# module.net
KiCad netlist of a schematic drawn in Altium Designer
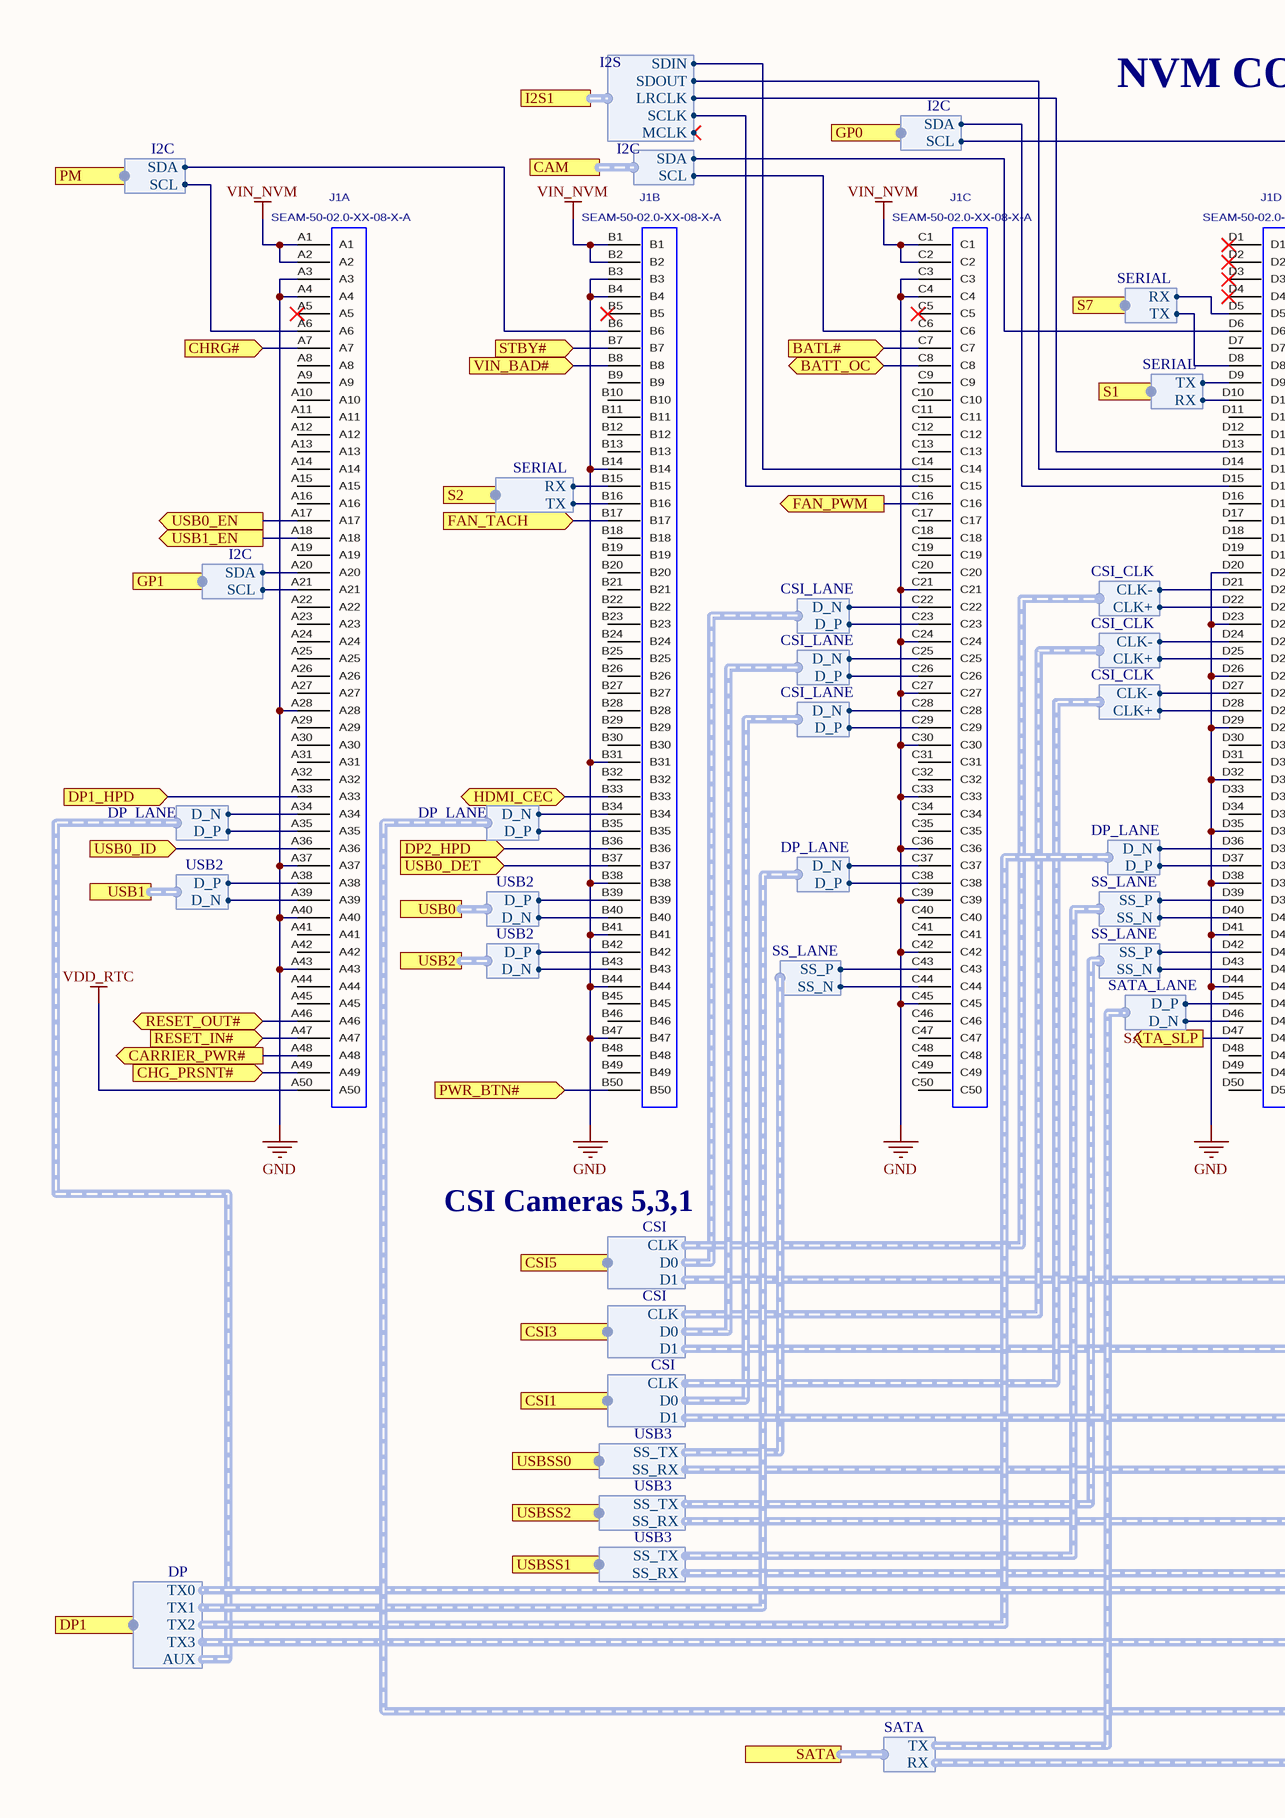
[diagram p0: module.SchDoc, left]
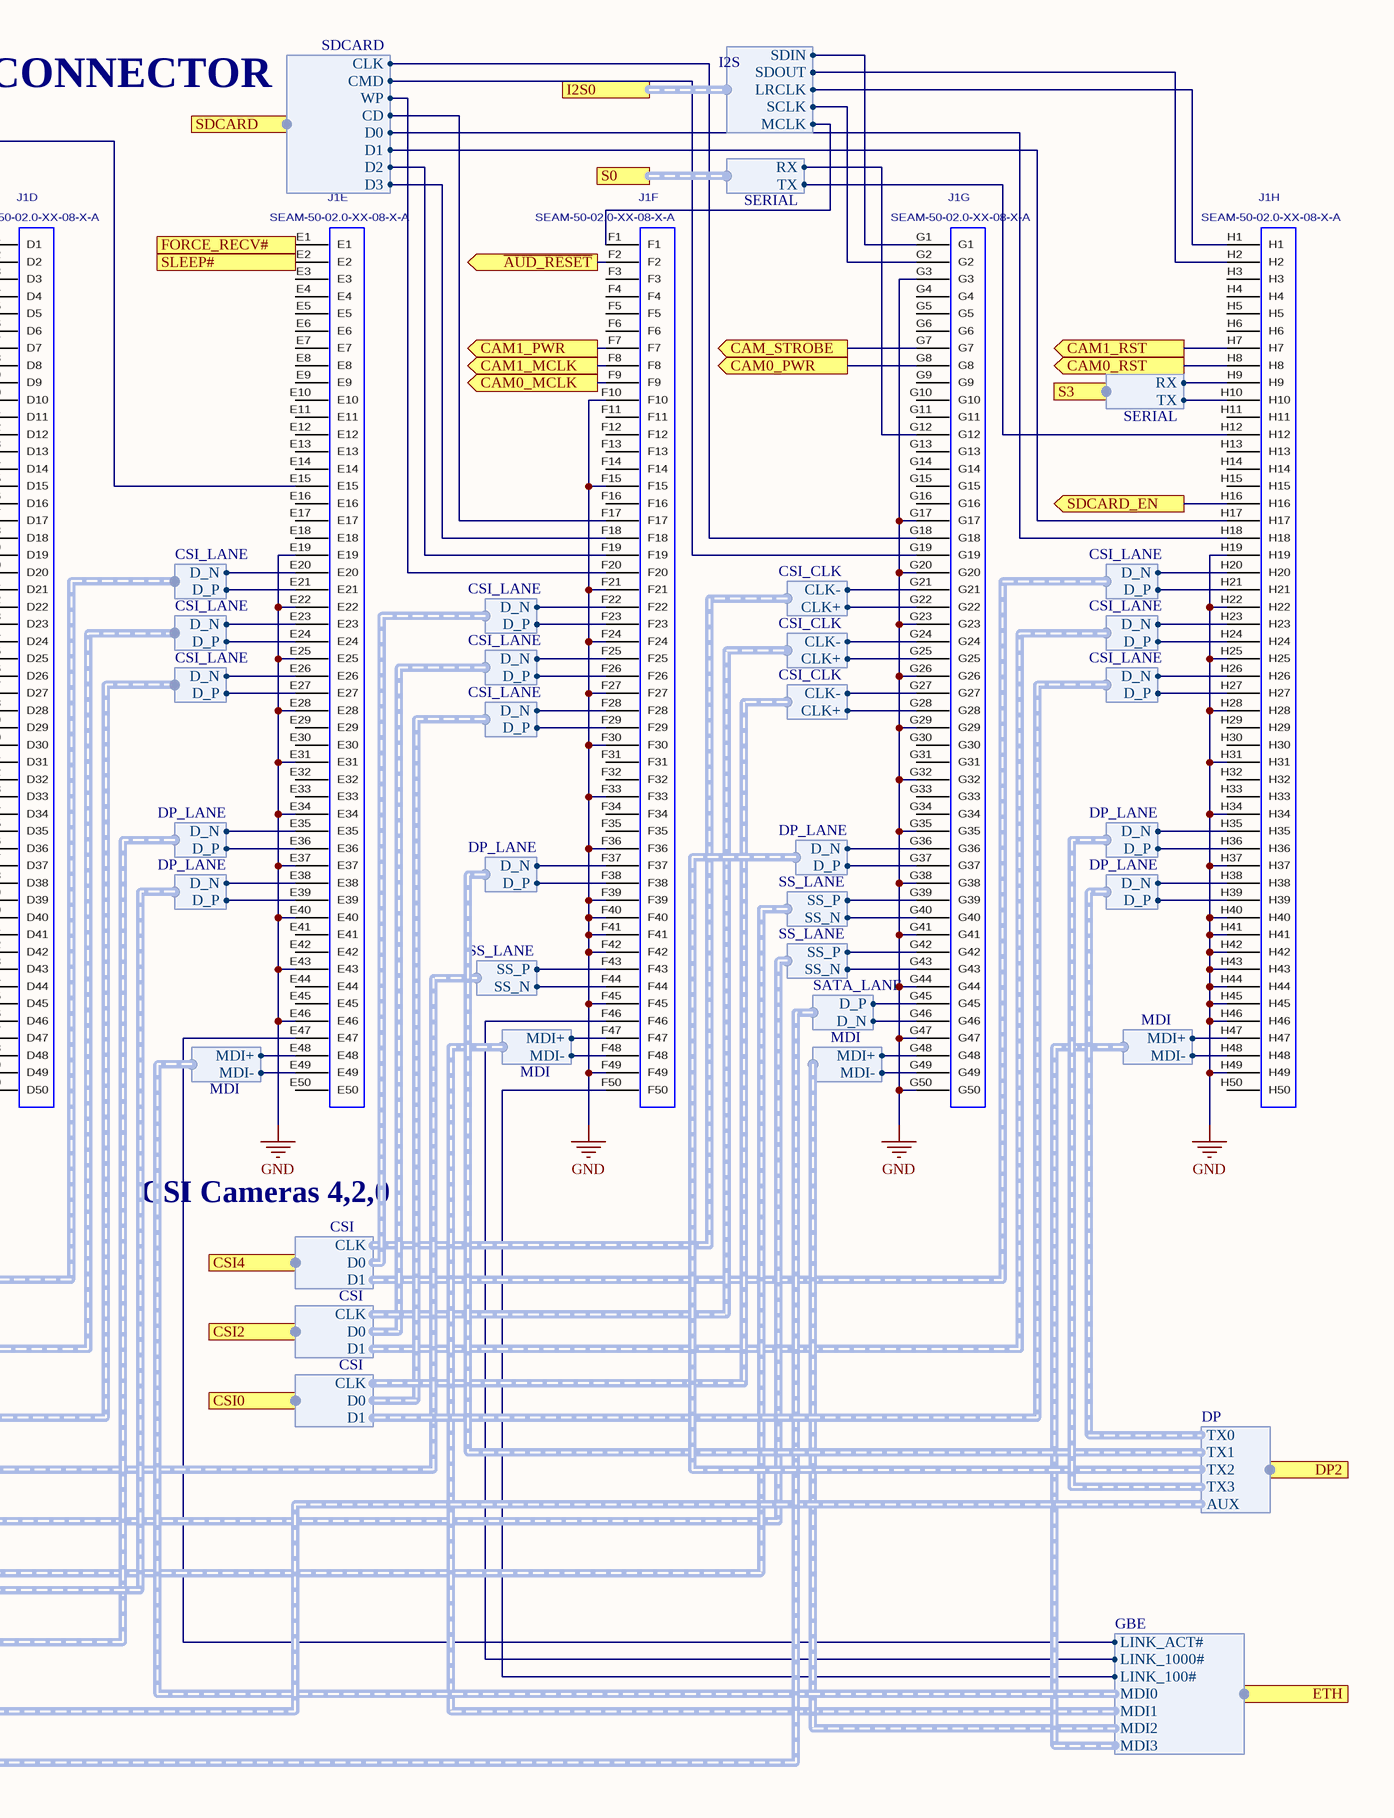
[diagram p1: module.SchDoc, right]

(export (version "E")
  (design (tool "Eeschema 10.0.6"))
  (components
    (comp (ref "J1")
      (value "SEAM-50-02.0-XX-08-X-A")
      (footprint "SEAM-50-02.0-XX-08-X-A")
      (description "0.050\" TERMINAL ASSEMBLY.")
      (fields (field (name "MANUFACTURER") "SAMTEC") (field (name "CREATED") "December 10, 2015 -Wendy Xin"))
      (libsource (lib "SEAM-50-02.0-XX-08-X-A") (part "SEAM-50-02.0-XX-08-X-A"))
    )
  )
  (nets
    (net (code "26") (name "/AUD_RESET") (class "Default")
      (node (ref "J1") (pin "F2") (pinfunction "F2_F2") (pintype "passive"))
    )
    (net (code "27") (name "/BATL#") (class "Default")
      (node (ref "J1") (pin "C7") (pinfunction "C7_C7") (pintype "passive"))
    )
    (net (code "28") (name "/BATT_OC") (class "Default")
      (node (ref "J1") (pin "C8") (pinfunction "C8_C8") (pintype "passive"))
    )
    (net (code "29") (name "/CAM0_MCLK") (class "Default")
      (node (ref "J1") (pin "F9") (pinfunction "F9_F9") (pintype "passive"))
    )
    (net (code "30") (name "/CAM0_PWR") (class "Default")
      (node (ref "J1") (pin "G8") (pinfunction "G8_G8") (pintype "passive"))
    )
    (net (code "31") (name "/CAM0_RST") (class "Default")
      (node (ref "J1") (pin "H8") (pinfunction "H8_H8") (pintype "passive"))
    )
    (net (code "32") (name "/CAM1_MCLK") (class "Default")
      (node (ref "J1") (pin "F8") (pinfunction "F8_F8") (pintype "passive"))
    )
    (net (code "33") (name "/CAM1_PWR") (class "Default")
      (node (ref "J1") (pin "F7") (pinfunction "F7_F7") (pintype "passive"))
    )
    (net (code "34") (name "/CAM1_RST") (class "Default")
      (node (ref "J1") (pin "H7") (pinfunction "H7_H7") (pintype "passive"))
    )
    (net (code "35") (name "/CAM_STROBE") (class "Default")
      (node (ref "J1") (pin "G7") (pinfunction "G7_G7") (pintype "passive"))
    )
    (net (code "36") (name "/CARRIER_PWR#") (class "Default")
      (node (ref "J1") (pin "A48") (pinfunction "A48_A48") (pintype "passive"))
    )
    (net (code "37") (name "/CD") (class "Default")
      (node (ref "J1") (pin "F17") (pinfunction "F17_F17") (pintype "passive"))
    )
    (net (code "38") (name "/CHG_PRSNT#") (class "Default")
      (node (ref "J1") (pin "A49") (pinfunction "A49_A49") (pintype "passive"))
    )
    (net (code "39") (name "/CHRG#") (class "Default")
      (node (ref "J1") (pin "A7") (pinfunction "A7_A7") (pintype "passive"))
    )
    (net (code "40") (name "/CMD") (class "Default")
      (node (ref "J1") (pin "G19") (pinfunction "G19_G19") (pintype "passive"))
    )
    (net (code "47") (name "/D2") (class "Default")
      (node (ref "J1") (pin "F19") (pinfunction "F19_F19") (pintype "passive"))
    )
    (net (code "48") (name "/D3") (class "Default")
      (node (ref "J1") (pin "F18") (pinfunction "F18_F18") (pintype "passive"))
    )
    (net (code "49") (name "/DP1_HPD") (class "Default")
      (node (ref "J1") (pin "A33") (pinfunction "A33_A33") (pintype "passive"))
    )
    (net (code "51") (name "/DP2_HPD") (class "Default")
      (node (ref "J1") (pin "B36") (pinfunction "B36_B36") (pintype "passive"))
    )
    (net (code "54") (name "/FAN_PWM") (class "Default")
      (node (ref "J1") (pin "C16") (pinfunction "C16_C16") (pintype "passive"))
    )
    (net (code "55") (name "/FAN_TACH") (class "Default")
      (node (ref "J1") (pin "B17") (pinfunction "B17_B17") (pintype "passive"))
    )
    (net (code "56") (name "/FORCE_RECV#") (class "Default")
      (node (ref "J1") (pin "E1") (pinfunction "E1_E1") (pintype "passive"))
    )
    (net (code "57") (name "/HDMI_CEC") (class "Default")
      (node (ref "J1") (pin "B33") (pinfunction "B33_B33") (pintype "passive"))
    )
    (net (code "59") (name "/LINK_100#") (class "Default")
      (node (ref "J1") (pin "F50") (pinfunction "F50_F50") (pintype "passive"))
    )
    (net (code "60") (name "/LINK_1000#") (class "Default")
      (node (ref "J1") (pin "F46") (pinfunction "F46_F46") (pintype "passive"))
    )
    (net (code "61") (name "/LINK_ACT#") (class "Default")
      (node (ref "J1") (pin "E47") (pinfunction "E47_E47") (pintype "passive"))
    )
    (net (code "62") (name "/PWR_BTN#") (class "Default")
      (node (ref "J1") (pin "B50") (pinfunction "B50_B50") (pintype "passive"))
    )
    (net (code "63") (name "/RESET_IN#") (class "Default")
      (node (ref "J1") (pin "A47") (pinfunction "A47_A47") (pintype "passive"))
    )
    (net (code "64") (name "/RESET_OUT#") (class "Default")
      (node (ref "J1") (pin "A46") (pinfunction "A46_A46") (pintype "passive"))
    )
    (net (code "65") (name "/SATA_SLP") (class "Default")
      (node (ref "J1") (pin "D47") (pinfunction "D47_D47") (pintype "passive"))
    )
    (net (code "67") (name "/SDCARD_EN") (class "Default")
      (node (ref "J1") (pin "H16") (pinfunction "H16_H16") (pintype "passive"))
    )
    (net (code "68") (name "/SLEEP#") (class "Default")
      (node (ref "J1") (pin "E2") (pinfunction "E2_E2") (pintype "passive"))
    )
    (net (code "69") (name "/STBY#") (class "Default")
      (node (ref "J1") (pin "B7") (pinfunction "B7_B7") (pintype "passive"))
    )
    (net (code "70") (name "/USB0_DET") (class "Default")
      (node (ref "J1") (pin "B37") (pinfunction "B37_B37") (pintype "passive"))
    )
    (net (code "71") (name "/USB0_EN") (class "Default")
      (node (ref "J1") (pin "A17") (pinfunction "A17_A17") (pintype "passive"))
    )
    (net (code "72") (name "/USB0_ID") (class "Default")
      (node (ref "J1") (pin "A36") (pinfunction "A36_A36") (pintype "passive"))
    )
    (net (code "73") (name "/USB1_EN") (class "Default")
      (node (ref "J1") (pin "A18") (pinfunction "A18_A18") (pintype "passive"))
    )
    (net (code "77") (name "/VIN_BAD#") (class "Default")
      (node (ref "J1") (pin "B8") (pinfunction "B8_B8") (pintype "passive"))
    )
    (net (code "78") (name "/WP") (class "Default")
      (node (ref "J1") (pin "F20") (pinfunction "F20_F20") (pintype "passive"))
    )
    (net (code "90") (name "GND") (class "Default")
      (node (ref "J1") (pin "A28") (pinfunction "A28_A28") (pintype "passive"))
      (node (ref "J1") (pin "A3") (pinfunction "A3_A3") (pintype "passive"))
      (node (ref "J1") (pin "A37") (pinfunction "A37_A37") (pintype "passive"))
      (node (ref "J1") (pin "A4") (pinfunction "A4_A4") (pintype "passive"))
      (node (ref "J1") (pin "A40") (pinfunction "A40_A40") (pintype "passive"))
      (node (ref "J1") (pin "A43") (pinfunction "A43_A43") (pintype "passive"))
      (node (ref "J1") (pin "B14") (pinfunction "B14_B14") (pintype "passive"))
      (node (ref "J1") (pin "B3") (pinfunction "B3_B3") (pintype "passive"))
      (node (ref "J1") (pin "B31") (pinfunction "B31_B31") (pintype "passive"))
      (node (ref "J1") (pin "B38") (pinfunction "B38_B38") (pintype "passive"))
      (node (ref "J1") (pin "B4") (pinfunction "B4_B4") (pintype "passive"))
      (node (ref "J1") (pin "B41") (pinfunction "B41_B41") (pintype "passive"))
      (node (ref "J1") (pin "B44") (pinfunction "B44_B44") (pintype "passive"))
      (node (ref "J1") (pin "B47") (pinfunction "B47_B47") (pintype "passive"))
      (node (ref "J1") (pin "C21") (pinfunction "C21_C21") (pintype "passive"))
      (node (ref "J1") (pin "C24") (pinfunction "C24_C24") (pintype "passive"))
      (node (ref "J1") (pin "C27") (pinfunction "C27_C27") (pintype "passive"))
      (node (ref "J1") (pin "C3") (pinfunction "C3_C3") (pintype "passive"))
      (node (ref "J1") (pin "C30") (pinfunction "C30_C30") (pintype "passive"))
      (node (ref "J1") (pin "C33") (pinfunction "C33_C33") (pintype "passive"))
      (node (ref "J1") (pin "C36") (pinfunction "C36_C36") (pintype "passive"))
      (node (ref "J1") (pin "C39") (pinfunction "C39_C39") (pintype "passive"))
      (node (ref "J1") (pin "C4") (pinfunction "C4_C4") (pintype "passive"))
      (node (ref "J1") (pin "C42") (pinfunction "C42_C42") (pintype "passive"))
      (node (ref "J1") (pin "C45") (pinfunction "C45_C45") (pintype "passive"))
      (node (ref "J1") (pin "D20") (pinfunction "D20_D20") (pintype "passive"))
      (node (ref "J1") (pin "D23") (pinfunction "D23_D23") (pintype "passive"))
      (node (ref "J1") (pin "D26") (pinfunction "D26_D26") (pintype "passive"))
      (node (ref "J1") (pin "D29") (pinfunction "D29_D29") (pintype "passive"))
      (node (ref "J1") (pin "D32") (pinfunction "D32_D32") (pintype "passive"))
      (node (ref "J1") (pin "D35") (pinfunction "D35_D35") (pintype "passive"))
      (node (ref "J1") (pin "D38") (pinfunction "D38_D38") (pintype "passive"))
      (node (ref "J1") (pin "D41") (pinfunction "D41_D41") (pintype "passive"))
      (node (ref "J1") (pin "D44") (pinfunction "D44_D44") (pintype "passive"))
      (node (ref "J1") (pin "E19") (pinfunction "E19_E19") (pintype "passive"))
      (node (ref "J1") (pin "E22") (pinfunction "E22_E22") (pintype "passive"))
      (node (ref "J1") (pin "E25") (pinfunction "E25_E25") (pintype "passive"))
      (node (ref "J1") (pin "E28") (pinfunction "E28_E28") (pintype "passive"))
      (node (ref "J1") (pin "E31") (pinfunction "E31_E31") (pintype "passive"))
      (node (ref "J1") (pin "E34") (pinfunction "E34_E34") (pintype "passive"))
      (node (ref "J1") (pin "E37") (pinfunction "E37_E37") (pintype "passive"))
      (node (ref "J1") (pin "E40") (pinfunction "E40_E40") (pintype "passive"))
      (node (ref "J1") (pin "E43") (pinfunction "E43_E43") (pintype "passive"))
      (node (ref "J1") (pin "E46") (pinfunction "E46_E46") (pintype "passive"))
      (node (ref "J1") (pin "F10") (pinfunction "F10_F10") (pintype "passive"))
      (node (ref "J1") (pin "F15") (pinfunction "F15_F15") (pintype "passive"))
      (node (ref "J1") (pin "F21") (pinfunction "F21_F21") (pintype "passive"))
      (node (ref "J1") (pin "F24") (pinfunction "F24_F24") (pintype "passive"))
      (node (ref "J1") (pin "F27") (pinfunction "F27_F27") (pintype "passive"))
      (node (ref "J1") (pin "F30") (pinfunction "F30_F30") (pintype "passive"))
      (node (ref "J1") (pin "F33") (pinfunction "F33_F33") (pintype "passive"))
      (node (ref "J1") (pin "F36") (pinfunction "F36_F36") (pintype "passive"))
      (node (ref "J1") (pin "F39") (pinfunction "F39_F39") (pintype "passive"))
      (node (ref "J1") (pin "F40") (pinfunction "F40_F40") (pintype "passive"))
      (node (ref "J1") (pin "F41") (pinfunction "F41_F41") (pintype "passive"))
      (node (ref "J1") (pin "F42") (pinfunction "F42_F42") (pintype "passive"))
      (node (ref "J1") (pin "F45") (pinfunction "F45_F45") (pintype "passive"))
      (node (ref "J1") (pin "F49") (pinfunction "F49_F49") (pintype "passive"))
      (node (ref "J1") (pin "G17") (pinfunction "G17_G17") (pintype "passive"))
      (node (ref "J1") (pin "G20") (pinfunction "G20_G20") (pintype "passive"))
      (node (ref "J1") (pin "G23") (pinfunction "G23_G23") (pintype "passive"))
      (node (ref "J1") (pin "G26") (pinfunction "G26_G26") (pintype "passive"))
      (node (ref "J1") (pin "G29") (pinfunction "G29_G29") (pintype "passive"))
      (node (ref "J1") (pin "G3") (pinfunction "G3_G3") (pintype "passive"))
      (node (ref "J1") (pin "G32") (pinfunction "G32_G32") (pintype "passive"))
      (node (ref "J1") (pin "G35") (pinfunction "G35_G35") (pintype "passive"))
      (node (ref "J1") (pin "G38") (pinfunction "G38_G38") (pintype "passive"))
      (node (ref "J1") (pin "G41") (pinfunction "G41_G41") (pintype "passive"))
      (node (ref "J1") (pin "G44") (pinfunction "G44_G44") (pintype "passive"))
      (node (ref "J1") (pin "G47") (pinfunction "G47_G47") (pintype "passive"))
      (node (ref "J1") (pin "G50") (pinfunction "G50_G50") (pintype "passive"))
      (node (ref "J1") (pin "H19") (pinfunction "H19_H19") (pintype "passive"))
      (node (ref "J1") (pin "H22") (pinfunction "H22_H22") (pintype "passive"))
      (node (ref "J1") (pin "H25") (pinfunction "H25_H25") (pintype "passive"))
      (node (ref "J1") (pin "H28") (pinfunction "H28_H28") (pintype "passive"))
      (node (ref "J1") (pin "H31") (pinfunction "H31_H31") (pintype "passive"))
      (node (ref "J1") (pin "H34") (pinfunction "H34_H34") (pintype "passive"))
      (node (ref "J1") (pin "H37") (pinfunction "H37_H37") (pintype "passive"))
      (node (ref "J1") (pin "H40") (pinfunction "H40_H40") (pintype "passive"))
      (node (ref "J1") (pin "H41") (pinfunction "H41_H41") (pintype "passive"))
      (node (ref "J1") (pin "H42") (pinfunction "H42_H42") (pintype "passive"))
      (node (ref "J1") (pin "H43") (pinfunction "H43_H43") (pintype "passive"))
      (node (ref "J1") (pin "H44") (pinfunction "H44_H44") (pintype "passive"))
      (node (ref "J1") (pin "H45") (pinfunction "H45_H45") (pintype "passive"))
      (node (ref "J1") (pin "H46") (pinfunction "H46_H46") (pintype "passive"))
      (node (ref "J1") (pin "H49") (pinfunction "H49_H49") (pintype "passive"))
    )
    (net (code "91") (name "VDD_RTC") (class "Default")
      (node (ref "J1") (pin "A50") (pinfunction "A50_A50") (pintype "passive"))
    )
    (net (code "92") (name "VIN_NVM") (class "Default")
      (node (ref "J1") (pin "A1") (pinfunction "A1_A1") (pintype "passive"))
      (node (ref "J1") (pin "A2") (pinfunction "A2_A2") (pintype "passive"))
      (node (ref "J1") (pin "B1") (pinfunction "B1_B1") (pintype "passive"))
      (node (ref "J1") (pin "B2") (pinfunction "B2_B2") (pintype "passive"))
      (node (ref "J1") (pin "C1") (pinfunction "C1_C1") (pintype "passive"))
      (node (ref "J1") (pin "C2") (pinfunction "C2_C2") (pintype "passive"))
    )
    (net (code "93") (name "unconnected-(J1-PadA5)") (class "Default")
      (node (ref "J1") (pin "A5") (pinfunction "A5_A5") (pintype "passive+no_connect"))
    )
    (net (code "94") (name "unconnected-(J1-PadA6)") (class "Default")
      (node (ref "J1") (pin "A6") (pinfunction "A6_A6") (pintype "passive"))
    )
    (net (code "95") (name "unconnected-(J1-PadA8)") (class "Default")
      (node (ref "J1") (pin "A8") (pinfunction "A8_A8") (pintype "passive"))
    )
    (net (code "96") (name "unconnected-(J1-PadA9)") (class "Default")
      (node (ref "J1") (pin "A9") (pinfunction "A9_A9") (pintype "passive"))
    )
    (net (code "97") (name "unconnected-(J1-PadA10)") (class "Default")
      (node (ref "J1") (pin "A10") (pinfunction "A10_A10") (pintype "passive"))
    )
    (net (code "98") (name "unconnected-(J1-PadA11)") (class "Default")
      (node (ref "J1") (pin "A11") (pinfunction "A11_A11") (pintype "passive"))
    )
    (net (code "99") (name "unconnected-(J1-PadA12)") (class "Default")
      (node (ref "J1") (pin "A12") (pinfunction "A12_A12") (pintype "passive"))
    )
    (net (code "100") (name "unconnected-(J1-PadA13)") (class "Default")
      (node (ref "J1") (pin "A13") (pinfunction "A13_A13") (pintype "passive"))
    )
    (net (code "101") (name "unconnected-(J1-PadA14)") (class "Default")
      (node (ref "J1") (pin "A14") (pinfunction "A14_A14") (pintype "passive"))
    )
    (net (code "102") (name "unconnected-(J1-PadA15)") (class "Default")
      (node (ref "J1") (pin "A15") (pinfunction "A15_A15") (pintype "passive"))
    )
    (net (code "103") (name "unconnected-(J1-PadA16)") (class "Default")
      (node (ref "J1") (pin "A16") (pinfunction "A16_A16") (pintype "passive"))
    )
    (net (code "104") (name "unconnected-(J1-PadA19)") (class "Default")
      (node (ref "J1") (pin "A19") (pinfunction "A19_A19") (pintype "passive"))
    )
    (net (code "105") (name "unconnected-(J1-PadA20)") (class "Default")
      (node (ref "J1") (pin "A20") (pinfunction "A20_A20") (pintype "passive"))
    )
    (net (code "106") (name "unconnected-(J1-PadA21)") (class "Default")
      (node (ref "J1") (pin "A21") (pinfunction "A21_A21") (pintype "passive"))
    )
    (net (code "107") (name "unconnected-(J1-PadA22)") (class "Default")
      (node (ref "J1") (pin "A22") (pinfunction "A22_A22") (pintype "passive"))
    )
    (net (code "108") (name "unconnected-(J1-PadA23)") (class "Default")
      (node (ref "J1") (pin "A23") (pinfunction "A23_A23") (pintype "passive"))
    )
    (net (code "109") (name "unconnected-(J1-PadA24)") (class "Default")
      (node (ref "J1") (pin "A24") (pinfunction "A24_A24") (pintype "passive"))
    )
    (net (code "110") (name "unconnected-(J1-PadA25)") (class "Default")
      (node (ref "J1") (pin "A25") (pinfunction "A25_A25") (pintype "passive"))
    )
    (net (code "111") (name "unconnected-(J1-PadA26)") (class "Default")
      (node (ref "J1") (pin "A26") (pinfunction "A26_A26") (pintype "passive"))
    )
    (net (code "112") (name "unconnected-(J1-PadA27)") (class "Default")
      (node (ref "J1") (pin "A27") (pinfunction "A27_A27") (pintype "passive"))
    )
    (net (code "113") (name "unconnected-(J1-PadA29)") (class "Default")
      (node (ref "J1") (pin "A29") (pinfunction "A29_A29") (pintype "passive"))
    )
    (net (code "114") (name "unconnected-(J1-PadA30)") (class "Default")
      (node (ref "J1") (pin "A30") (pinfunction "A30_A30") (pintype "passive"))
    )
    (net (code "115") (name "unconnected-(J1-PadA31)") (class "Default")
      (node (ref "J1") (pin "A31") (pinfunction "A31_A31") (pintype "passive"))
    )
    (net (code "116") (name "unconnected-(J1-PadA32)") (class "Default")
      (node (ref "J1") (pin "A32") (pinfunction "A32_A32") (pintype "passive"))
    )
    (net (code "117") (name "unconnected-(J1-PadA34)") (class "Default")
      (node (ref "J1") (pin "A34") (pinfunction "A34_A34") (pintype "passive"))
    )
    (net (code "118") (name "unconnected-(J1-PadA35)") (class "Default")
      (node (ref "J1") (pin "A35") (pinfunction "A35_A35") (pintype "passive"))
    )
    (net (code "119") (name "unconnected-(J1-PadA38)") (class "Default")
      (node (ref "J1") (pin "A38") (pinfunction "A38_A38") (pintype "passive"))
    )
    (net (code "120") (name "unconnected-(J1-PadA39)") (class "Default")
      (node (ref "J1") (pin "A39") (pinfunction "A39_A39") (pintype "passive"))
    )
    (net (code "121") (name "unconnected-(J1-PadA41)") (class "Default")
      (node (ref "J1") (pin "A41") (pinfunction "A41_A41") (pintype "passive"))
    )
    (net (code "122") (name "unconnected-(J1-PadA42)") (class "Default")
      (node (ref "J1") (pin "A42") (pinfunction "A42_A42") (pintype "passive"))
    )
    (net (code "123") (name "unconnected-(J1-PadA44)") (class "Default")
      (node (ref "J1") (pin "A44") (pinfunction "A44_A44") (pintype "passive"))
    )
    (net (code "124") (name "unconnected-(J1-PadA45)") (class "Default")
      (node (ref "J1") (pin "A45") (pinfunction "A45_A45") (pintype "passive"))
    )
    (net (code "125") (name "unconnected-(J1-PadB5)") (class "Default")
      (node (ref "J1") (pin "B5") (pinfunction "B5_B5") (pintype "passive+no_connect"))
    )
    (net (code "126") (name "unconnected-(J1-PadB6)") (class "Default")
      (node (ref "J1") (pin "B6") (pinfunction "B6_B6") (pintype "passive"))
    )
    (net (code "127") (name "unconnected-(J1-PadB9)") (class "Default")
      (node (ref "J1") (pin "B9") (pinfunction "B9_B9") (pintype "passive"))
    )
    (net (code "128") (name "unconnected-(J1-PadB10)") (class "Default")
      (node (ref "J1") (pin "B10") (pinfunction "B10_B10") (pintype "passive"))
    )
    (net (code "129") (name "unconnected-(J1-PadB11)") (class "Default")
      (node (ref "J1") (pin "B11") (pinfunction "B11_B11") (pintype "passive"))
    )
    (net (code "130") (name "unconnected-(J1-PadB12)") (class "Default")
      (node (ref "J1") (pin "B12") (pinfunction "B12_B12") (pintype "passive"))
    )
    (net (code "131") (name "unconnected-(J1-PadB13)") (class "Default")
      (node (ref "J1") (pin "B13") (pinfunction "B13_B13") (pintype "passive"))
    )
    (net (code "132") (name "unconnected-(J1-PadB15)") (class "Default")
      (node (ref "J1") (pin "B15") (pinfunction "B15_B15") (pintype "passive"))
    )
    (net (code "133") (name "unconnected-(J1-PadB16)") (class "Default")
      (node (ref "J1") (pin "B16") (pinfunction "B16_B16") (pintype "passive"))
    )
    (net (code "134") (name "unconnected-(J1-PadB18)") (class "Default")
      (node (ref "J1") (pin "B18") (pinfunction "B18_B18") (pintype "passive"))
    )
    (net (code "135") (name "unconnected-(J1-PadB19)") (class "Default")
      (node (ref "J1") (pin "B19") (pinfunction "B19_B19") (pintype "passive"))
    )
    (net (code "136") (name "unconnected-(J1-PadB20)") (class "Default")
      (node (ref "J1") (pin "B20") (pinfunction "B20_B20") (pintype "passive"))
    )
    (net (code "137") (name "unconnected-(J1-PadB21)") (class "Default")
      (node (ref "J1") (pin "B21") (pinfunction "B21_B21") (pintype "passive"))
    )
    (net (code "138") (name "unconnected-(J1-PadB22)") (class "Default")
      (node (ref "J1") (pin "B22") (pinfunction "B22_B22") (pintype "passive"))
    )
    (net (code "139") (name "unconnected-(J1-PadB23)") (class "Default")
      (node (ref "J1") (pin "B23") (pinfunction "B23_B23") (pintype "passive"))
    )
    (net (code "140") (name "unconnected-(J1-PadB24)") (class "Default")
      (node (ref "J1") (pin "B24") (pinfunction "B24_B24") (pintype "passive"))
    )
    (net (code "141") (name "unconnected-(J1-PadB25)") (class "Default")
      (node (ref "J1") (pin "B25") (pinfunction "B25_B25") (pintype "passive"))
    )
    (net (code "142") (name "unconnected-(J1-PadB26)") (class "Default")
      (node (ref "J1") (pin "B26") (pinfunction "B26_B26") (pintype "passive"))
    )
    (net (code "143") (name "unconnected-(J1-PadB27)") (class "Default")
      (node (ref "J1") (pin "B27") (pinfunction "B27_B27") (pintype "passive"))
    )
    (net (code "144") (name "unconnected-(J1-PadB28)") (class "Default")
      (node (ref "J1") (pin "B28") (pinfunction "B28_B28") (pintype "passive"))
    )
    (net (code "145") (name "unconnected-(J1-PadB29)") (class "Default")
      (node (ref "J1") (pin "B29") (pinfunction "B29_B29") (pintype "passive"))
    )
    (net (code "146") (name "unconnected-(J1-PadB30)") (class "Default")
      (node (ref "J1") (pin "B30") (pinfunction "B30_B30") (pintype "passive"))
    )
    (net (code "147") (name "unconnected-(J1-PadB32)") (class "Default")
      (node (ref "J1") (pin "B32") (pinfunction "B32_B32") (pintype "passive"))
    )
    (net (code "148") (name "unconnected-(J1-PadB34)") (class "Default")
      (node (ref "J1") (pin "B34") (pinfunction "B34_B34") (pintype "passive"))
    )
    (net (code "149") (name "unconnected-(J1-PadB35)") (class "Default")
      (node (ref "J1") (pin "B35") (pinfunction "B35_B35") (pintype "passive"))
    )
    (net (code "150") (name "unconnected-(J1-PadB39)") (class "Default")
      (node (ref "J1") (pin "B39") (pinfunction "B39_B39") (pintype "passive"))
    )
    (net (code "151") (name "unconnected-(J1-PadB40)") (class "Default")
      (node (ref "J1") (pin "B40") (pinfunction "B40_B40") (pintype "passive"))
    )
    (net (code "152") (name "unconnected-(J1-PadB42)") (class "Default")
      (node (ref "J1") (pin "B42") (pinfunction "B42_B42") (pintype "passive"))
    )
    (net (code "153") (name "unconnected-(J1-PadB43)") (class "Default")
      (node (ref "J1") (pin "B43") (pinfunction "B43_B43") (pintype "passive"))
    )
    (net (code "154") (name "unconnected-(J1-PadB45)") (class "Default")
      (node (ref "J1") (pin "B45") (pinfunction "B45_B45") (pintype "passive"))
    )
    (net (code "155") (name "unconnected-(J1-PadB46)") (class "Default")
      (node (ref "J1") (pin "B46") (pinfunction "B46_B46") (pintype "passive"))
    )
    (net (code "156") (name "unconnected-(J1-PadB48)") (class "Default")
      (node (ref "J1") (pin "B48") (pinfunction "B48_B48") (pintype "passive"))
    )
    (net (code "157") (name "unconnected-(J1-PadB49)") (class "Default")
      (node (ref "J1") (pin "B49") (pinfunction "B49_B49") (pintype "passive"))
    )
    (net (code "158") (name "unconnected-(J1-PadC5)") (class "Default")
      (node (ref "J1") (pin "C5") (pinfunction "C5_C5") (pintype "passive+no_connect"))
    )
    (net (code "159") (name "unconnected-(J1-PadC6)") (class "Default")
      (node (ref "J1") (pin "C6") (pinfunction "C6_C6") (pintype "passive"))
    )
    (net (code "160") (name "unconnected-(J1-PadC9)") (class "Default")
      (node (ref "J1") (pin "C9") (pinfunction "C9_C9") (pintype "passive"))
    )
    (net (code "161") (name "unconnected-(J1-PadC10)") (class "Default")
      (node (ref "J1") (pin "C10") (pinfunction "C10_C10") (pintype "passive"))
    )
    (net (code "162") (name "unconnected-(J1-PadC11)") (class "Default")
      (node (ref "J1") (pin "C11") (pinfunction "C11_C11") (pintype "passive"))
    )
    (net (code "163") (name "unconnected-(J1-PadC12)") (class "Default")
      (node (ref "J1") (pin "C12") (pinfunction "C12_C12") (pintype "passive"))
    )
    (net (code "164") (name "unconnected-(J1-PadC13)") (class "Default")
      (node (ref "J1") (pin "C13") (pinfunction "C13_C13") (pintype "passive"))
    )
    (net (code "165") (name "unconnected-(J1-PadC14)") (class "Default")
      (node (ref "J1") (pin "C14") (pinfunction "C14_C14") (pintype "passive"))
    )
    (net (code "166") (name "unconnected-(J1-PadC15)") (class "Default")
      (node (ref "J1") (pin "C15") (pinfunction "C15_C15") (pintype "passive"))
    )
    (net (code "167") (name "unconnected-(J1-PadC17)") (class "Default")
      (node (ref "J1") (pin "C17") (pinfunction "C17_C17") (pintype "passive"))
    )
    (net (code "168") (name "unconnected-(J1-PadC18)") (class "Default")
      (node (ref "J1") (pin "C18") (pinfunction "C18_C18") (pintype "passive"))
    )
    (net (code "169") (name "unconnected-(J1-PadC19)") (class "Default")
      (node (ref "J1") (pin "C19") (pinfunction "C19_C19") (pintype "passive"))
    )
    (net (code "170") (name "unconnected-(J1-PadC20)") (class "Default")
      (node (ref "J1") (pin "C20") (pinfunction "C20_C20") (pintype "passive"))
    )
    (net (code "171") (name "unconnected-(J1-PadC22)") (class "Default")
      (node (ref "J1") (pin "C22") (pinfunction "C22_C22") (pintype "passive"))
    )
    (net (code "172") (name "unconnected-(J1-PadC23)") (class "Default")
      (node (ref "J1") (pin "C23") (pinfunction "C23_C23") (pintype "passive"))
    )
    (net (code "173") (name "unconnected-(J1-PadC25)") (class "Default")
      (node (ref "J1") (pin "C25") (pinfunction "C25_C25") (pintype "passive"))
    )
    (net (code "174") (name "unconnected-(J1-PadC26)") (class "Default")
      (node (ref "J1") (pin "C26") (pinfunction "C26_C26") (pintype "passive"))
    )
    (net (code "175") (name "unconnected-(J1-PadC28)") (class "Default")
      (node (ref "J1") (pin "C28") (pinfunction "C28_C28") (pintype "passive"))
    )
    (net (code "176") (name "unconnected-(J1-PadC29)") (class "Default")
      (node (ref "J1") (pin "C29") (pinfunction "C29_C29") (pintype "passive"))
    )
    (net (code "177") (name "unconnected-(J1-PadC31)") (class "Default")
      (node (ref "J1") (pin "C31") (pinfunction "C31_C31") (pintype "passive"))
    )
    (net (code "178") (name "unconnected-(J1-PadC32)") (class "Default")
      (node (ref "J1") (pin "C32") (pinfunction "C32_C32") (pintype "passive"))
    )
    (net (code "179") (name "unconnected-(J1-PadC34)") (class "Default")
      (node (ref "J1") (pin "C34") (pinfunction "C34_C34") (pintype "passive"))
    )
    (net (code "180") (name "unconnected-(J1-PadC35)") (class "Default")
      (node (ref "J1") (pin "C35") (pinfunction "C35_C35") (pintype "passive"))
    )
    (net (code "181") (name "unconnected-(J1-PadC37)") (class "Default")
      (node (ref "J1") (pin "C37") (pinfunction "C37_C37") (pintype "passive"))
    )
    (net (code "182") (name "unconnected-(J1-PadC38)") (class "Default")
      (node (ref "J1") (pin "C38") (pinfunction "C38_C38") (pintype "passive"))
    )
    (net (code "183") (name "unconnected-(J1-PadC40)") (class "Default")
      (node (ref "J1") (pin "C40") (pinfunction "C40_C40") (pintype "passive"))
    )
    (net (code "184") (name "unconnected-(J1-PadC41)") (class "Default")
      (node (ref "J1") (pin "C41") (pinfunction "C41_C41") (pintype "passive"))
    )
    (net (code "185") (name "unconnected-(J1-PadC43)") (class "Default")
      (node (ref "J1") (pin "C43") (pinfunction "C43_C43") (pintype "passive"))
    )
    (net (code "186") (name "unconnected-(J1-PadC44)") (class "Default")
      (node (ref "J1") (pin "C44") (pinfunction "C44_C44") (pintype "passive"))
    )
    (net (code "187") (name "unconnected-(J1-PadC46)") (class "Default")
      (node (ref "J1") (pin "C46") (pinfunction "C46_C46") (pintype "passive"))
    )
    (net (code "188") (name "unconnected-(J1-PadC47)") (class "Default")
      (node (ref "J1") (pin "C47") (pinfunction "C47_C47") (pintype "passive"))
    )
    (net (code "189") (name "unconnected-(J1-PadC48)") (class "Default")
      (node (ref "J1") (pin "C48") (pinfunction "C48_C48") (pintype "passive"))
    )
    (net (code "190") (name "unconnected-(J1-PadC49)") (class "Default")
      (node (ref "J1") (pin "C49") (pinfunction "C49_C49") (pintype "passive"))
    )
    (net (code "191") (name "unconnected-(J1-PadC50)") (class "Default")
      (node (ref "J1") (pin "C50") (pinfunction "C50_C50") (pintype "passive"))
    )
    (net (code "192") (name "unconnected-(J1-PadD1)") (class "Default")
      (node (ref "J1") (pin "D1") (pinfunction "D1_D1") (pintype "passive+no_connect"))
    )
    (net (code "193") (name "unconnected-(J1-PadD2)") (class "Default")
      (node (ref "J1") (pin "D2") (pinfunction "D2_D2") (pintype "passive+no_connect"))
    )
    (net (code "194") (name "unconnected-(J1-PadD3)") (class "Default")
      (node (ref "J1") (pin "D3") (pinfunction "D3_D3") (pintype "passive+no_connect"))
    )
    (net (code "195") (name "unconnected-(J1-PadD4)") (class "Default")
      (node (ref "J1") (pin "D4") (pinfunction "D4_D4") (pintype "passive+no_connect"))
    )
    (net (code "196") (name "unconnected-(J1-PadD5)") (class "Default")
      (node (ref "J1") (pin "D5") (pinfunction "D5_D5") (pintype "passive"))
    )
    (net (code "197") (name "unconnected-(J1-PadD6)") (class "Default")
      (node (ref "J1") (pin "D6") (pinfunction "D6_D6") (pintype "passive"))
    )
    (net (code "198") (name "unconnected-(J1-PadD7)") (class "Default")
      (node (ref "J1") (pin "D7") (pinfunction "D7_D7") (pintype "passive"))
    )
    (net (code "199") (name "unconnected-(J1-PadD8)") (class "Default")
      (node (ref "J1") (pin "D8") (pinfunction "D8_D8") (pintype "passive"))
    )
    (net (code "200") (name "unconnected-(J1-PadD9)") (class "Default")
      (node (ref "J1") (pin "D9") (pinfunction "D9_D9") (pintype "passive"))
    )
    (net (code "201") (name "unconnected-(J1-PadD10)") (class "Default")
      (node (ref "J1") (pin "D10") (pinfunction "D10_D10") (pintype "passive"))
    )
    (net (code "202") (name "unconnected-(J1-PadD11)") (class "Default")
      (node (ref "J1") (pin "D11") (pinfunction "D11_D11") (pintype "passive"))
    )
    (net (code "203") (name "unconnected-(J1-PadD12)") (class "Default")
      (node (ref "J1") (pin "D12") (pinfunction "D12_D12") (pintype "passive"))
    )
    (net (code "204") (name "unconnected-(J1-PadD13)") (class "Default")
      (node (ref "J1") (pin "D13") (pinfunction "D13_D13") (pintype "passive"))
    )
    (net (code "205") (name "unconnected-(J1-PadD14)") (class "Default")
      (node (ref "J1") (pin "D14") (pinfunction "D14_D14") (pintype "passive"))
    )
    (net (code "206") (name "unconnected-(J1-PadD15)") (class "Default")
      (node (ref "J1") (pin "D15") (pinfunction "D15_D15") (pintype "passive"))
    )
    (net (code "207") (name "unconnected-(J1-PadD16)") (class "Default")
      (node (ref "J1") (pin "D16") (pinfunction "D16_D16") (pintype "passive"))
    )
    (net (code "208") (name "unconnected-(J1-PadD17)") (class "Default")
      (node (ref "J1") (pin "D17") (pinfunction "D17_D17") (pintype "passive"))
    )
    (net (code "209") (name "unconnected-(J1-PadD18)") (class "Default")
      (node (ref "J1") (pin "D18") (pinfunction "D18_D18") (pintype "passive"))
    )
    (net (code "210") (name "unconnected-(J1-PadD19)") (class "Default")
      (node (ref "J1") (pin "D19") (pinfunction "D19_D19") (pintype "passive"))
    )
    (net (code "211") (name "unconnected-(J1-PadD21)") (class "Default")
      (node (ref "J1") (pin "D21") (pinfunction "D21_D21") (pintype "passive"))
    )
    (net (code "212") (name "unconnected-(J1-PadD22)") (class "Default")
      (node (ref "J1") (pin "D22") (pinfunction "D22_D22") (pintype "passive"))
    )
    (net (code "213") (name "unconnected-(J1-PadD24)") (class "Default")
      (node (ref "J1") (pin "D24") (pinfunction "D24_D24") (pintype "passive"))
    )
    (net (code "214") (name "unconnected-(J1-PadD25)") (class "Default")
      (node (ref "J1") (pin "D25") (pinfunction "D25_D25") (pintype "passive"))
    )
    (net (code "215") (name "unconnected-(J1-PadD27)") (class "Default")
      (node (ref "J1") (pin "D27") (pinfunction "D27_D27") (pintype "passive"))
    )
    (net (code "216") (name "unconnected-(J1-PadD28)") (class "Default")
      (node (ref "J1") (pin "D28") (pinfunction "D28_D28") (pintype "passive"))
    )
    (net (code "217") (name "unconnected-(J1-PadD30)") (class "Default")
      (node (ref "J1") (pin "D30") (pinfunction "D30_D30") (pintype "passive"))
    )
    (net (code "218") (name "unconnected-(J1-PadD31)") (class "Default")
      (node (ref "J1") (pin "D31") (pinfunction "D31_D31") (pintype "passive"))
    )
    (net (code "219") (name "unconnected-(J1-PadD33)") (class "Default")
      (node (ref "J1") (pin "D33") (pinfunction "D33_D33") (pintype "passive"))
    )
    (net (code "220") (name "unconnected-(J1-PadD34)") (class "Default")
      (node (ref "J1") (pin "D34") (pinfunction "D34_D34") (pintype "passive"))
    )
    (net (code "221") (name "unconnected-(J1-PadD36)") (class "Default")
      (node (ref "J1") (pin "D36") (pinfunction "D36_D36") (pintype "passive"))
    )
    (net (code "222") (name "unconnected-(J1-PadD37)") (class "Default")
      (node (ref "J1") (pin "D37") (pinfunction "D37_D37") (pintype "passive"))
    )
    (net (code "223") (name "unconnected-(J1-PadD39)") (class "Default")
      (node (ref "J1") (pin "D39") (pinfunction "D39_D39") (pintype "passive"))
    )
    (net (code "224") (name "unconnected-(J1-PadD40)") (class "Default")
      (node (ref "J1") (pin "D40") (pinfunction "D40_D40") (pintype "passive"))
    )
    (net (code "225") (name "unconnected-(J1-PadD42)") (class "Default")
      (node (ref "J1") (pin "D42") (pinfunction "D42_D42") (pintype "passive"))
    )
    (net (code "226") (name "unconnected-(J1-PadD43)") (class "Default")
      (node (ref "J1") (pin "D43") (pinfunction "D43_D43") (pintype "passive"))
    )
    (net (code "227") (name "unconnected-(J1-PadD45)") (class "Default")
      (node (ref "J1") (pin "D45") (pinfunction "D45_D45") (pintype "passive"))
    )
    (net (code "228") (name "unconnected-(J1-PadD46)") (class "Default")
      (node (ref "J1") (pin "D46") (pinfunction "D46_D46") (pintype "passive"))
    )
    (net (code "229") (name "unconnected-(J1-PadD48)") (class "Default")
      (node (ref "J1") (pin "D48") (pinfunction "D48_D48") (pintype "passive"))
    )
    (net (code "230") (name "unconnected-(J1-PadD49)") (class "Default")
      (node (ref "J1") (pin "D49") (pinfunction "D49_D49") (pintype "passive"))
    )
    (net (code "231") (name "unconnected-(J1-PadD50)") (class "Default")
      (node (ref "J1") (pin "D50") (pinfunction "D50_D50") (pintype "passive"))
    )
    (net (code "232") (name "unconnected-(J1-PadE3)") (class "Default")
      (node (ref "J1") (pin "E3") (pinfunction "E3_E3") (pintype "passive"))
    )
    (net (code "233") (name "unconnected-(J1-PadE4)") (class "Default")
      (node (ref "J1") (pin "E4") (pinfunction "E4_E4") (pintype "passive"))
    )
    (net (code "234") (name "unconnected-(J1-PadE5)") (class "Default")
      (node (ref "J1") (pin "E5") (pinfunction "E5_E5") (pintype "passive"))
    )
    (net (code "235") (name "unconnected-(J1-PadE6)") (class "Default")
      (node (ref "J1") (pin "E6") (pinfunction "E6_E6") (pintype "passive"))
    )
    (net (code "236") (name "unconnected-(J1-PadE7)") (class "Default")
      (node (ref "J1") (pin "E7") (pinfunction "E7_E7") (pintype "passive"))
    )
    (net (code "237") (name "unconnected-(J1-PadE8)") (class "Default")
      (node (ref "J1") (pin "E8") (pinfunction "E8_E8") (pintype "passive"))
    )
    (net (code "238") (name "unconnected-(J1-PadE9)") (class "Default")
      (node (ref "J1") (pin "E9") (pinfunction "E9_E9") (pintype "passive"))
    )
    (net (code "239") (name "unconnected-(J1-PadE10)") (class "Default")
      (node (ref "J1") (pin "E10") (pinfunction "E10_E10") (pintype "passive"))
    )
    (net (code "240") (name "unconnected-(J1-PadE11)") (class "Default")
      (node (ref "J1") (pin "E11") (pinfunction "E11_E11") (pintype "passive"))
    )
    (net (code "241") (name "unconnected-(J1-PadE12)") (class "Default")
      (node (ref "J1") (pin "E12") (pinfunction "E12_E12") (pintype "passive"))
    )
    (net (code "242") (name "unconnected-(J1-PadE13)") (class "Default")
      (node (ref "J1") (pin "E13") (pinfunction "E13_E13") (pintype "passive"))
    )
    (net (code "243") (name "unconnected-(J1-PadE14)") (class "Default")
      (node (ref "J1") (pin "E14") (pinfunction "E14_E14") (pintype "passive"))
    )
    (net (code "244") (name "unconnected-(J1-PadE15)") (class "Default")
      (node (ref "J1") (pin "E15") (pinfunction "E15_E15") (pintype "passive"))
    )
    (net (code "245") (name "unconnected-(J1-PadE16)") (class "Default")
      (node (ref "J1") (pin "E16") (pinfunction "E16_E16") (pintype "passive"))
    )
    (net (code "246") (name "unconnected-(J1-PadE17)") (class "Default")
      (node (ref "J1") (pin "E17") (pinfunction "E17_E17") (pintype "passive"))
    )
    (net (code "247") (name "unconnected-(J1-PadE18)") (class "Default")
      (node (ref "J1") (pin "E18") (pinfunction "E18_E18") (pintype "passive"))
    )
    (net (code "248") (name "unconnected-(J1-PadE20)") (class "Default")
      (node (ref "J1") (pin "E20") (pinfunction "E20_E20") (pintype "passive"))
    )
    (net (code "249") (name "unconnected-(J1-PadE21)") (class "Default")
      (node (ref "J1") (pin "E21") (pinfunction "E21_E21") (pintype "passive"))
    )
    (net (code "250") (name "unconnected-(J1-PadE23)") (class "Default")
      (node (ref "J1") (pin "E23") (pinfunction "E23_E23") (pintype "passive"))
    )
    (net (code "251") (name "unconnected-(J1-PadE24)") (class "Default")
      (node (ref "J1") (pin "E24") (pinfunction "E24_E24") (pintype "passive"))
    )
    (net (code "252") (name "unconnected-(J1-PadE26)") (class "Default")
      (node (ref "J1") (pin "E26") (pinfunction "E26_E26") (pintype "passive"))
    )
    (net (code "253") (name "unconnected-(J1-PadE27)") (class "Default")
      (node (ref "J1") (pin "E27") (pinfunction "E27_E27") (pintype "passive"))
    )
    (net (code "254") (name "unconnected-(J1-PadE29)") (class "Default")
      (node (ref "J1") (pin "E29") (pinfunction "E29_E29") (pintype "passive"))
    )
    (net (code "255") (name "unconnected-(J1-PadE30)") (class "Default")
      (node (ref "J1") (pin "E30") (pinfunction "E30_E30") (pintype "passive"))
    )
    (net (code "256") (name "unconnected-(J1-PadE32)") (class "Default")
      (node (ref "J1") (pin "E32") (pinfunction "E32_E32") (pintype "passive"))
    )
    (net (code "257") (name "unconnected-(J1-PadE33)") (class "Default")
      (node (ref "J1") (pin "E33") (pinfunction "E33_E33") (pintype "passive"))
    )
    (net (code "258") (name "unconnected-(J1-PadE35)") (class "Default")
      (node (ref "J1") (pin "E35") (pinfunction "E35_E35") (pintype "passive"))
    )
    (net (code "259") (name "unconnected-(J1-PadE36)") (class "Default")
      (node (ref "J1") (pin "E36") (pinfunction "E36_E36") (pintype "passive"))
    )
    (net (code "260") (name "unconnected-(J1-PadE38)") (class "Default")
      (node (ref "J1") (pin "E38") (pinfunction "E38_E38") (pintype "passive"))
    )
    (net (code "261") (name "unconnected-(J1-PadE39)") (class "Default")
      (node (ref "J1") (pin "E39") (pinfunction "E39_E39") (pintype "passive"))
    )
    (net (code "262") (name "unconnected-(J1-PadE41)") (class "Default")
      (node (ref "J1") (pin "E41") (pinfunction "E41_E41") (pintype "passive"))
    )
    (net (code "263") (name "unconnected-(J1-PadE42)") (class "Default")
      (node (ref "J1") (pin "E42") (pinfunction "E42_E42") (pintype "passive"))
    )
    (net (code "264") (name "unconnected-(J1-PadE44)") (class "Default")
      (node (ref "J1") (pin "E44") (pinfunction "E44_E44") (pintype "passive"))
    )
    (net (code "265") (name "unconnected-(J1-PadE45)") (class "Default")
      (node (ref "J1") (pin "E45") (pinfunction "E45_E45") (pintype "passive"))
    )
    (net (code "266") (name "unconnected-(J1-PadE48)") (class "Default")
      (node (ref "J1") (pin "E48") (pinfunction "E48_E48") (pintype "passive"))
    )
    (net (code "267") (name "unconnected-(J1-PadE49)") (class "Default")
      (node (ref "J1") (pin "E49") (pinfunction "E49_E49") (pintype "passive"))
    )
    (net (code "268") (name "unconnected-(J1-PadE50)") (class "Default")
      (node (ref "J1") (pin "E50") (pinfunction "E50_E50") (pintype "passive"))
    )
    (net (code "269") (name "unconnected-(J1-PadF1)") (class "Default")
      (node (ref "J1") (pin "F1") (pinfunction "F1_F1") (pintype "passive"))
    )
    (net (code "270") (name "unconnected-(J1-PadF3)") (class "Default")
      (node (ref "J1") (pin "F3") (pinfunction "F3_F3") (pintype "passive"))
    )
    (net (code "271") (name "unconnected-(J1-PadF4)") (class "Default")
      (node (ref "J1") (pin "F4") (pinfunction "F4_F4") (pintype "passive"))
    )
    (net (code "272") (name "unconnected-(J1-PadF5)") (class "Default")
      (node (ref "J1") (pin "F5") (pinfunction "F5_F5") (pintype "passive"))
    )
    (net (code "273") (name "unconnected-(J1-PadF6)") (class "Default")
      (node (ref "J1") (pin "F6") (pinfunction "F6_F6") (pintype "passive"))
    )
    (net (code "274") (name "unconnected-(J1-PadF11)") (class "Default")
      (node (ref "J1") (pin "F11") (pinfunction "F11_F11") (pintype "passive"))
    )
    (net (code "275") (name "unconnected-(J1-PadF12)") (class "Default")
      (node (ref "J1") (pin "F12") (pinfunction "F12_F12") (pintype "passive"))
    )
    (net (code "276") (name "unconnected-(J1-PadF13)") (class "Default")
      (node (ref "J1") (pin "F13") (pinfunction "F13_F13") (pintype "passive"))
    )
    (net (code "277") (name "unconnected-(J1-PadF14)") (class "Default")
      (node (ref "J1") (pin "F14") (pinfunction "F14_F14") (pintype "passive"))
    )
    (net (code "278") (name "unconnected-(J1-PadF16)") (class "Default")
      (node (ref "J1") (pin "F16") (pinfunction "F16_F16") (pintype "passive"))
    )
    (net (code "279") (name "unconnected-(J1-PadF22)") (class "Default")
      (node (ref "J1") (pin "F22") (pinfunction "F22_F22") (pintype "passive"))
    )
    (net (code "280") (name "unconnected-(J1-PadF23)") (class "Default")
      (node (ref "J1") (pin "F23") (pinfunction "F23_F23") (pintype "passive"))
    )
    (net (code "281") (name "unconnected-(J1-PadF25)") (class "Default")
      (node (ref "J1") (pin "F25") (pinfunction "F25_F25") (pintype "passive"))
    )
    (net (code "282") (name "unconnected-(J1-PadF26)") (class "Default")
      (node (ref "J1") (pin "F26") (pinfunction "F26_F26") (pintype "passive"))
    )
    (net (code "283") (name "unconnected-(J1-PadF28)") (class "Default")
      (node (ref "J1") (pin "F28") (pinfunction "F28_F28") (pintype "passive"))
    )
    (net (code "284") (name "unconnected-(J1-PadF29)") (class "Default")
      (node (ref "J1") (pin "F29") (pinfunction "F29_F29") (pintype "passive"))
    )
    (net (code "285") (name "unconnected-(J1-PadF31)") (class "Default")
      (node (ref "J1") (pin "F31") (pinfunction "F31_F31") (pintype "passive"))
    )
    (net (code "286") (name "unconnected-(J1-PadF32)") (class "Default")
      (node (ref "J1") (pin "F32") (pinfunction "F32_F32") (pintype "passive"))
    )
    (net (code "287") (name "unconnected-(J1-PadF34)") (class "Default")
      (node (ref "J1") (pin "F34") (pinfunction "F34_F34") (pintype "passive"))
    )
    (net (code "288") (name "unconnected-(J1-PadF35)") (class "Default")
      (node (ref "J1") (pin "F35") (pinfunction "F35_F35") (pintype "passive"))
    )
    (net (code "289") (name "unconnected-(J1-PadF37)") (class "Default")
      (node (ref "J1") (pin "F37") (pinfunction "F37_F37") (pintype "passive"))
    )
    (net (code "290") (name "unconnected-(J1-PadF38)") (class "Default")
      (node (ref "J1") (pin "F38") (pinfunction "F38_F38") (pintype "passive"))
    )
    (net (code "291") (name "unconnected-(J1-PadF43)") (class "Default")
      (node (ref "J1") (pin "F43") (pinfunction "F43_F43") (pintype "passive"))
    )
    (net (code "292") (name "unconnected-(J1-PadF44)") (class "Default")
      (node (ref "J1") (pin "F44") (pinfunction "F44_F44") (pintype "passive"))
    )
    (net (code "293") (name "unconnected-(J1-PadF47)") (class "Default")
      (node (ref "J1") (pin "F47") (pinfunction "F47_F47") (pintype "passive"))
    )
    (net (code "294") (name "unconnected-(J1-PadF48)") (class "Default")
      (node (ref "J1") (pin "F48") (pinfunction "F48_F48") (pintype "passive"))
    )
    (net (code "295") (name "unconnected-(J1-PadG1)") (class "Default")
      (node (ref "J1") (pin "G1") (pinfunction "G1_G1") (pintype "passive"))
    )
    (net (code "296") (name "unconnected-(J1-PadG2)") (class "Default")
      (node (ref "J1") (pin "G2") (pinfunction "G2_G2") (pintype "passive"))
    )
    (net (code "297") (name "unconnected-(J1-PadG4)") (class "Default")
      (node (ref "J1") (pin "G4") (pinfunction "G4_G4") (pintype "passive"))
    )
    (net (code "298") (name "unconnected-(J1-PadG5)") (class "Default")
      (node (ref "J1") (pin "G5") (pinfunction "G5_G5") (pintype "passive"))
    )
    (net (code "299") (name "unconnected-(J1-PadG6)") (class "Default")
      (node (ref "J1") (pin "G6") (pinfunction "G6_G6") (pintype "passive"))
    )
    (net (code "300") (name "unconnected-(J1-PadG9)") (class "Default")
      (node (ref "J1") (pin "G9") (pinfunction "G9_G9") (pintype "passive"))
    )
    (net (code "301") (name "unconnected-(J1-PadG10)") (class "Default")
      (node (ref "J1") (pin "G10") (pinfunction "G10_G10") (pintype "passive"))
    )
    (net (code "302") (name "unconnected-(J1-PadG11)") (class "Default")
      (node (ref "J1") (pin "G11") (pinfunction "G11_G11") (pintype "passive"))
    )
    (net (code "303") (name "unconnected-(J1-PadG12)") (class "Default")
      (node (ref "J1") (pin "G12") (pinfunction "G12_G12") (pintype "passive"))
    )
    (net (code "304") (name "unconnected-(J1-PadG13)") (class "Default")
      (node (ref "J1") (pin "G13") (pinfunction "G13_G13") (pintype "passive"))
    )
    (net (code "305") (name "unconnected-(J1-PadG14)") (class "Default")
      (node (ref "J1") (pin "G14") (pinfunction "G14_G14") (pintype "passive"))
    )
    (net (code "306") (name "unconnected-(J1-PadG15)") (class "Default")
      (node (ref "J1") (pin "G15") (pinfunction "G15_G15") (pintype "passive"))
    )
    (net (code "307") (name "unconnected-(J1-PadG16)") (class "Default")
      (node (ref "J1") (pin "G16") (pinfunction "G16_G16") (pintype "passive"))
    )
    (net (code "308") (name "unconnected-(J1-PadG18)") (class "Default")
      (node (ref "J1") (pin "G18") (pinfunction "G18_G18") (pintype "passive"))
    )
    (net (code "309") (name "unconnected-(J1-PadG21)") (class "Default")
      (node (ref "J1") (pin "G21") (pinfunction "G21_G21") (pintype "passive"))
    )
    (net (code "310") (name "unconnected-(J1-PadG22)") (class "Default")
      (node (ref "J1") (pin "G22") (pinfunction "G22_G22") (pintype "passive"))
    )
    (net (code "311") (name "unconnected-(J1-PadG24)") (class "Default")
      (node (ref "J1") (pin "G24") (pinfunction "G24_G24") (pintype "passive"))
    )
    (net (code "312") (name "unconnected-(J1-PadG25)") (class "Default")
      (node (ref "J1") (pin "G25") (pinfunction "G25_G25") (pintype "passive"))
    )
    (net (code "313") (name "unconnected-(J1-PadG27)") (class "Default")
      (node (ref "J1") (pin "G27") (pinfunction "G27_G27") (pintype "passive"))
    )
    (net (code "314") (name "unconnected-(J1-PadG28)") (class "Default")
      (node (ref "J1") (pin "G28") (pinfunction "G28_G28") (pintype "passive"))
    )
    (net (code "315") (name "unconnected-(J1-PadG30)") (class "Default")
      (node (ref "J1") (pin "G30") (pinfunction "G30_G30") (pintype "passive"))
    )
    (net (code "316") (name "unconnected-(J1-PadG31)") (class "Default")
      (node (ref "J1") (pin "G31") (pinfunction "G31_G31") (pintype "passive"))
    )
    (net (code "317") (name "unconnected-(J1-PadG33)") (class "Default")
      (node (ref "J1") (pin "G33") (pinfunction "G33_G33") (pintype "passive"))
    )
    (net (code "318") (name "unconnected-(J1-PadG34)") (class "Default")
      (node (ref "J1") (pin "G34") (pinfunction "G34_G34") (pintype "passive"))
    )
    (net (code "319") (name "unconnected-(J1-PadG36)") (class "Default")
      (node (ref "J1") (pin "G36") (pinfunction "G36_G36") (pintype "passive"))
    )
    (net (code "320") (name "unconnected-(J1-PadG37)") (class "Default")
      (node (ref "J1") (pin "G37") (pinfunction "G37_G37") (pintype "passive"))
    )
    (net (code "321") (name "unconnected-(J1-PadG39)") (class "Default")
      (node (ref "J1") (pin "G39") (pinfunction "G39_G39") (pintype "passive"))
    )
    (net (code "322") (name "unconnected-(J1-PadG40)") (class "Default")
      (node (ref "J1") (pin "G40") (pinfunction "G40_G40") (pintype "passive"))
    )
    (net (code "323") (name "unconnected-(J1-PadG42)") (class "Default")
      (node (ref "J1") (pin "G42") (pinfunction "G42_G42") (pintype "passive"))
    )
    (net (code "324") (name "unconnected-(J1-PadG43)") (class "Default")
      (node (ref "J1") (pin "G43") (pinfunction "G43_G43") (pintype "passive"))
    )
    (net (code "325") (name "unconnected-(J1-PadG45)") (class "Default")
      (node (ref "J1") (pin "G45") (pinfunction "G45_G45") (pintype "passive"))
    )
    (net (code "326") (name "unconnected-(J1-PadG46)") (class "Default")
      (node (ref "J1") (pin "G46") (pinfunction "G46_G46") (pintype "passive"))
    )
    (net (code "327") (name "unconnected-(J1-PadG48)") (class "Default")
      (node (ref "J1") (pin "G48") (pinfunction "G48_G48") (pintype "passive"))
    )
    (net (code "328") (name "unconnected-(J1-PadG49)") (class "Default")
      (node (ref "J1") (pin "G49") (pinfunction "G49_G49") (pintype "passive"))
    )
    (net (code "329") (name "unconnected-(J1-PadH1)") (class "Default")
      (node (ref "J1") (pin "H1") (pinfunction "H1_H1") (pintype "passive"))
    )
    (net (code "330") (name "unconnected-(J1-PadH2)") (class "Default")
      (node (ref "J1") (pin "H2") (pinfunction "H2_H2") (pintype "passive"))
    )
    (net (code "331") (name "unconnected-(J1-PadH3)") (class "Default")
      (node (ref "J1") (pin "H3") (pinfunction "H3_H3") (pintype "passive"))
    )
    (net (code "332") (name "unconnected-(J1-PadH4)") (class "Default")
      (node (ref "J1") (pin "H4") (pinfunction "H4_H4") (pintype "passive"))
    )
    (net (code "333") (name "unconnected-(J1-PadH5)") (class "Default")
      (node (ref "J1") (pin "H5") (pinfunction "H5_H5") (pintype "passive"))
    )
    (net (code "334") (name "unconnected-(J1-PadH6)") (class "Default")
      (node (ref "J1") (pin "H6") (pinfunction "H6_H6") (pintype "passive"))
    )
    (net (code "335") (name "unconnected-(J1-PadH9)") (class "Default")
      (node (ref "J1") (pin "H9") (pinfunction "H9_H9") (pintype "passive"))
    )
    (net (code "336") (name "unconnected-(J1-PadH10)") (class "Default")
      (node (ref "J1") (pin "H10") (pinfunction "H10_H10") (pintype "passive"))
    )
    (net (code "337") (name "unconnected-(J1-PadH11)") (class "Default")
      (node (ref "J1") (pin "H11") (pinfunction "H11_H11") (pintype "passive"))
    )
    (net (code "338") (name "unconnected-(J1-PadH12)") (class "Default")
      (node (ref "J1") (pin "H12") (pinfunction "H12_H12") (pintype "passive"))
    )
    (net (code "339") (name "unconnected-(J1-PadH13)") (class "Default")
      (node (ref "J1") (pin "H13") (pinfunction "H13_H13") (pintype "passive"))
    )
    (net (code "340") (name "unconnected-(J1-PadH14)") (class "Default")
      (node (ref "J1") (pin "H14") (pinfunction "H14_H14") (pintype "passive"))
    )
    (net (code "341") (name "unconnected-(J1-PadH15)") (class "Default")
      (node (ref "J1") (pin "H15") (pinfunction "H15_H15") (pintype "passive"))
    )
    (net (code "342") (name "unconnected-(J1-PadH17)") (class "Default")
      (node (ref "J1") (pin "H17") (pinfunction "H17_H17") (pintype "passive"))
    )
    (net (code "343") (name "unconnected-(J1-PadH18)") (class "Default")
      (node (ref "J1") (pin "H18") (pinfunction "H18_H18") (pintype "passive"))
    )
    (net (code "344") (name "unconnected-(J1-PadH20)") (class "Default")
      (node (ref "J1") (pin "H20") (pinfunction "H20_H20") (pintype "passive"))
    )
    (net (code "345") (name "unconnected-(J1-PadH21)") (class "Default")
      (node (ref "J1") (pin "H21") (pinfunction "H21_H21") (pintype "passive"))
    )
    (net (code "346") (name "unconnected-(J1-PadH23)") (class "Default")
      (node (ref "J1") (pin "H23") (pinfunction "H23_H23") (pintype "passive"))
    )
    (net (code "347") (name "unconnected-(J1-PadH24)") (class "Default")
      (node (ref "J1") (pin "H24") (pinfunction "H24_H24") (pintype "passive"))
    )
    (net (code "348") (name "unconnected-(J1-PadH26)") (class "Default")
      (node (ref "J1") (pin "H26") (pinfunction "H26_H26") (pintype "passive"))
    )
    (net (code "349") (name "unconnected-(J1-PadH27)") (class "Default")
      (node (ref "J1") (pin "H27") (pinfunction "H27_H27") (pintype "passive"))
    )
    (net (code "350") (name "unconnected-(J1-PadH29)") (class "Default")
      (node (ref "J1") (pin "H29") (pinfunction "H29_H29") (pintype "passive"))
    )
    (net (code "351") (name "unconnected-(J1-PadH30)") (class "Default")
      (node (ref "J1") (pin "H30") (pinfunction "H30_H30") (pintype "passive"))
    )
    (net (code "352") (name "unconnected-(J1-PadH32)") (class "Default")
      (node (ref "J1") (pin "H32") (pinfunction "H32_H32") (pintype "passive"))
    )
    (net (code "353") (name "unconnected-(J1-PadH33)") (class "Default")
      (node (ref "J1") (pin "H33") (pinfunction "H33_H33") (pintype "passive"))
    )
    (net (code "354") (name "unconnected-(J1-PadH35)") (class "Default")
      (node (ref "J1") (pin "H35") (pinfunction "H35_H35") (pintype "passive"))
    )
    (net (code "355") (name "unconnected-(J1-PadH36)") (class "Default")
      (node (ref "J1") (pin "H36") (pinfunction "H36_H36") (pintype "passive"))
    )
    (net (code "356") (name "unconnected-(J1-PadH38)") (class "Default")
      (node (ref "J1") (pin "H38") (pinfunction "H38_H38") (pintype "passive"))
    )
    (net (code "357") (name "unconnected-(J1-PadH39)") (class "Default")
      (node (ref "J1") (pin "H39") (pinfunction "H39_H39") (pintype "passive"))
    )
    (net (code "358") (name "unconnected-(J1-PadH47)") (class "Default")
      (node (ref "J1") (pin "H47") (pinfunction "H47_H47") (pintype "passive"))
    )
    (net (code "359") (name "unconnected-(J1-PadH48)") (class "Default")
      (node (ref "J1") (pin "H48") (pinfunction "H48_H48") (pintype "passive"))
    )
    (net (code "360") (name "unconnected-(J1-PadH50)") (class "Default")
      (node (ref "J1") (pin "H50") (pinfunction "H50_H50") (pintype "passive"))
    )
  )
)
